# 06_POWER_5.net
KiCad netlist of a schematic drawn in Altium Designer
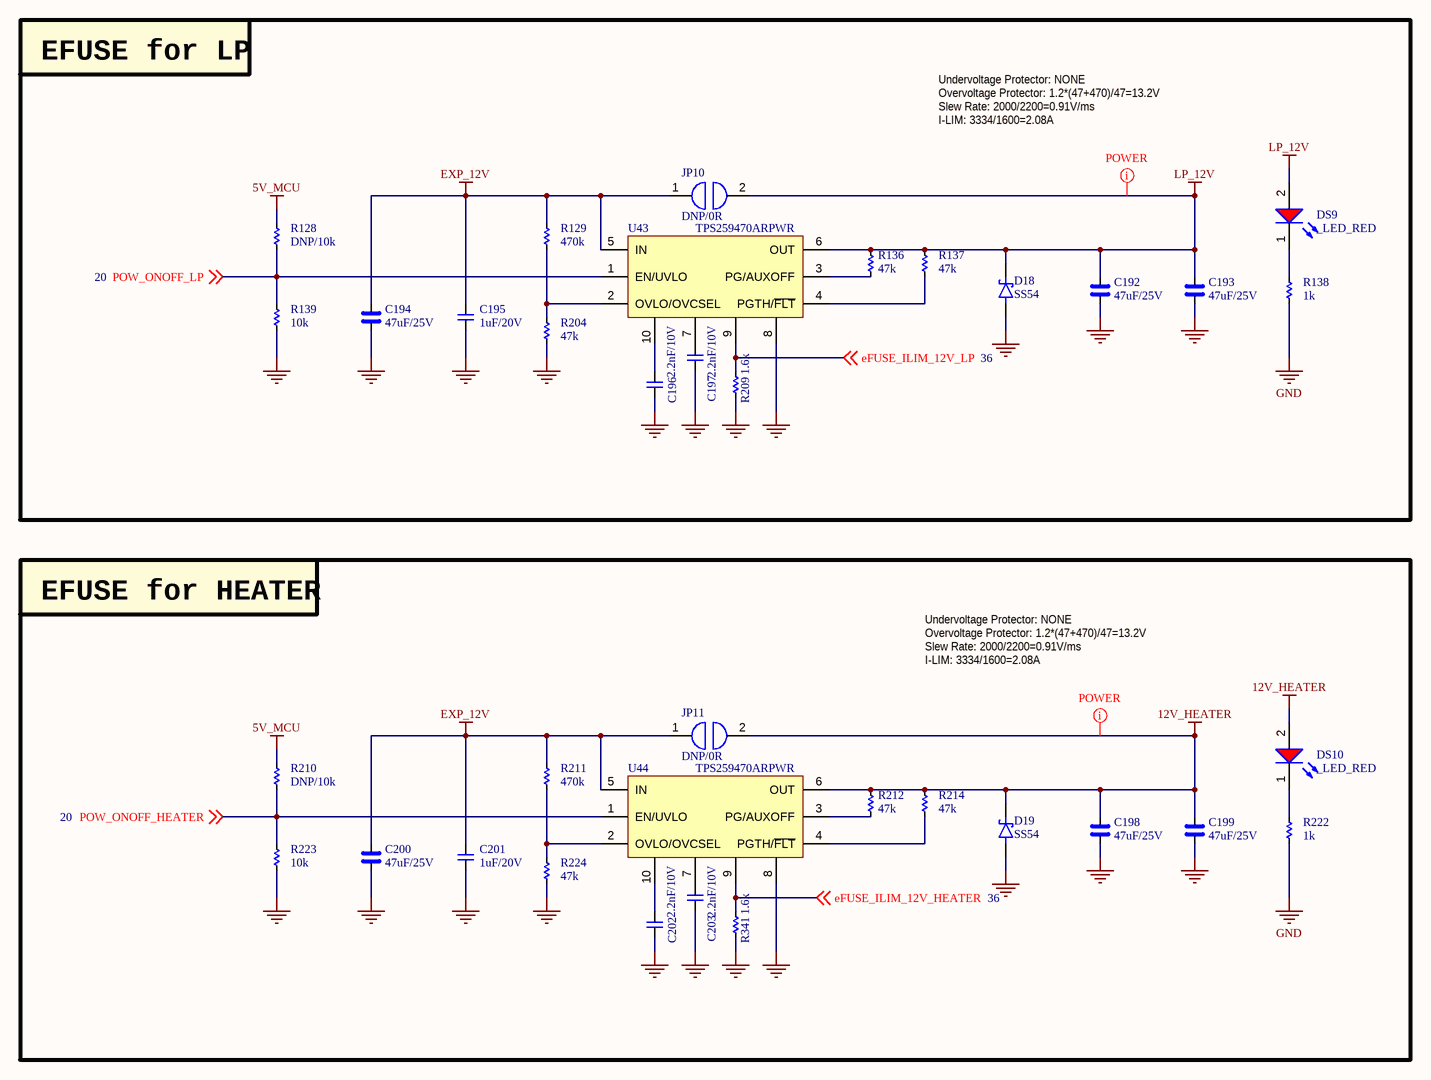
[diagram p0: 06_POWER_5.SchDoc]

(export (version "E")
  (design (tool "Eeschema 10.0.6"))
  (components
    (comp (ref "C192")
      (value "47uF/25V")
      (footprint "CAP_C_3225X80")
      (description "CAP High Value")
      (libsource (lib "LABLIB") (part "_CAP_C_High_2"))
    )
    (comp (ref "C193")
      (value "47uF/25V")
      (footprint "CAP_C_3225X80")
      (description "CAP High Value")
      (libsource (lib "LABLIB") (part "_CAP_C_High_2"))
    )
    (comp (ref "C194")
      (value "47uF/25V")
      (footprint "CAP_C_3225X80")
      (description "CAP High Value")
      (libsource (lib "LABLIB") (part "_CAP_C_High_2"))
    )
    (comp (ref "C195")
      (value "1uF/20V")
      (footprint "CAP_C_1005X60")
      (description "CAP")
      (libsource (lib "LABLIB") (part "_CAP_C_2"))
    )
    (comp (ref "C196")
      (value "2.2nF/10V")
      (footprint "CAP_C_1005X60")
      (description "CAP")
      (libsource (lib "LABLIB") (part "_CAP_C_2"))
    )
    (comp (ref "C197")
      (value "2.2nF/10V")
      (footprint "CAP_C_1005X60")
      (description "CAP")
      (libsource (lib "LABLIB") (part "_CAP_C_2"))
    )
    (comp (ref "C198")
      (value "47uF/25V")
      (footprint "CAP_C_3225X80")
      (description "CAP High Value")
      (libsource (lib "LABLIB") (part "_CAP_C_High_2"))
    )
    (comp (ref "C199")
      (value "47uF/25V")
      (footprint "CAP_C_3225X80")
      (description "CAP High Value")
      (libsource (lib "LABLIB") (part "_CAP_C_High_2"))
    )
    (comp (ref "C200")
      (value "47uF/25V")
      (footprint "CAP_C_3225X80")
      (description "CAP High Value")
      (libsource (lib "LABLIB") (part "_CAP_C_High_2"))
    )
    (comp (ref "C201")
      (value "1uF/20V")
      (footprint "CAP_C_1005X60")
      (description "CAP")
      (libsource (lib "LABLIB") (part "_CAP_C_2"))
    )
    (comp (ref "C202")
      (value "2.2nF/10V")
      (footprint "CAP_C_1005X60")
      (description "CAP")
      (libsource (lib "LABLIB") (part "_CAP_C_2"))
    )
    (comp (ref "C203")
      (value "2.2nF/10V")
      (footprint "CAP_C_1005X60")
      (description "CAP")
      (libsource (lib "LABLIB") (part "_CAP_C_2"))
    )
    (comp (ref "D18")
      (value "SS54")
      (footprint "DO-214AC_SMA")
      (description "DIODE SCHOTTKY")
      (libsource (lib "LABLIB") (part "DIODE SCHOTTKY"))
    )
    (comp (ref "D19")
      (value "SS54")
      (footprint "DO-214AC_SMA")
      (description "DIODE SCHOTTKY")
      (libsource (lib "LABLIB") (part "DIODE SCHOTTKY"))
    )
    (comp (ref "DS9") (value "_LED_RED") (footprint "LED_0603") (libsource (lib "LABLIB") (part "_LED_RED")))
    (comp (ref "DS10") (value "_LED_RED") (footprint "LED_0603") (libsource (lib "LABLIB") (part "_LED_RED")))
    (comp (ref "JP10") (value "DNP/0R") (footprint "JUMPER_1608") (libsource (lib "EXP_V1") (part "JUMPER")))
    (comp (ref "JP11") (value "DNP/0R") (footprint "JUMPER_1608") (libsource (lib "EXP_V1") (part "JUMPER")))
    (comp (ref "R128")
      (value "DNP/10k")
      (footprint "RES_C_1005X40")
      (description "RES")
      (libsource (lib "LABLIB") (part "_RES_B_2"))
    )
    (comp (ref "R129")
      (value "470k")
      (footprint "RES_C_1005X40")
      (description "RES")
      (libsource (lib "LABLIB") (part "_RES_B_2"))
    )
    (comp (ref "R136")
      (value "47k")
      (footprint "RES_C_1005X40")
      (description "RES")
      (libsource (lib "LABLIB") (part "_RES_B_2"))
    )
    (comp (ref "R137")
      (value "47k")
      (footprint "RES_C_1005X40")
      (description "RES")
      (libsource (lib "LABLIB") (part "_RES_B_2"))
    )
    (comp (ref "R138")
      (value "1k")
      (footprint "RES_C_1005X40")
      (description "RES")
      (libsource (lib "LABLIB") (part "_RES_B_2"))
    )
    (comp (ref "R139")
      (value "10k")
      (footprint "RES_C_1005X40")
      (description "RES")
      (libsource (lib "LABLIB") (part "_RES_B_2"))
    )
    (comp (ref "R204")
      (value "47k")
      (footprint "RES_C_1005X40")
      (description "RES")
      (libsource (lib "LABLIB") (part "_RES_B_2"))
    )
    (comp (ref "R209")
      (value "1.6k")
      (footprint "RES_C_1005X40")
      (description "RES")
      (libsource (lib "LABLIB") (part "_RES_B_2"))
    )
    (comp (ref "R210")
      (value "DNP/10k")
      (footprint "RES_C_1005X40")
      (description "RES")
      (libsource (lib "LABLIB") (part "_RES_B_2"))
    )
    (comp (ref "R211")
      (value "470k")
      (footprint "RES_C_1005X40")
      (description "RES")
      (libsource (lib "LABLIB") (part "_RES_B_2"))
    )
    (comp (ref "R212")
      (value "47k")
      (footprint "RES_C_1005X40")
      (description "RES")
      (libsource (lib "LABLIB") (part "_RES_B_2"))
    )
    (comp (ref "R214")
      (value "47k")
      (footprint "RES_C_1005X40")
      (description "RES")
      (libsource (lib "LABLIB") (part "_RES_B_2"))
    )
    (comp (ref "R222")
      (value "1k")
      (footprint "RES_C_1005X40")
      (description "RES")
      (libsource (lib "LABLIB") (part "_RES_B_2"))
    )
    (comp (ref "R223")
      (value "10k")
      (footprint "RES_C_1005X40")
      (description "RES")
      (libsource (lib "LABLIB") (part "_RES_B_2"))
    )
    (comp (ref "R224")
      (value "47k")
      (footprint "RES_C_1005X40")
      (description "RES")
      (libsource (lib "LABLIB") (part "_RES_B_2"))
    )
    (comp (ref "R341")
      (value "1.6k")
      (footprint "RES_C_1005X40")
      (description "RES")
      (libsource (lib "LABLIB") (part "_RES_B_2"))
    )
    (comp (ref "U43")
      (value "TPS259470ARPWR")
      (footprint "VQFN-HR-10")
      (libsource (lib "EXP_HW_V3") (part "TPS259470ARPWR"))
    )
    (comp (ref "U44")
      (value "TPS259470ARPWR")
      (footprint "VQFN-HR-10")
      (libsource (lib "EXP_HW_V3") (part "TPS259470ARPWR"))
    )
  )
  (nets
    (net (code "1") (name "5V_MCU") (class "Default")
      (node (ref "R128") (pin "1") (pinfunction "1_1") (pintype "passive"))
      (node (ref "R210") (pin "1") (pinfunction "1_1") (pintype "passive"))
    )
    (net (code "2") (name "12V_HEATER") (class "Default")
      (node (ref "C198") (pin "2") (pinfunction "2_2") (pintype "passive"))
      (node (ref "C199") (pin "2") (pinfunction "2_2") (pintype "passive"))
      (node (ref "D19") (pin "1") (pinfunction "K_1") (pintype "passive"))
      (node (ref "DS10") (pin "2") (pinfunction "A_2") (pintype "passive"))
      (node (ref "JP11") (pin "2") (pinfunction "2_2") (pintype "passive"))
      (node (ref "R212") (pin "2") (pinfunction "2_2") (pintype "passive"))
      (node (ref "R214") (pin "2") (pinfunction "2_2") (pintype "passive"))
      (node (ref "U44") (pin "6") (pinfunction "OUT_6") (pintype "passive"))
    )
    (net (code "3") (name "EXP_12V") (class "Default")
      (node (ref "C194") (pin "2") (pinfunction "2_2") (pintype "passive"))
      (node (ref "C195") (pin "2") (pinfunction "2_2") (pintype "passive"))
      (node (ref "C200") (pin "2") (pinfunction "2_2") (pintype "passive"))
      (node (ref "C201") (pin "2") (pinfunction "2_2") (pintype "passive"))
      (node (ref "JP10") (pin "1") (pinfunction "1_1") (pintype "passive"))
      (node (ref "JP11") (pin "1") (pinfunction "1_1") (pintype "passive"))
      (node (ref "R129") (pin "2") (pinfunction "2_2") (pintype "passive"))
      (node (ref "R211") (pin "2") (pinfunction "2_2") (pintype "passive"))
      (node (ref "U43") (pin "5") (pinfunction "IN_5") (pintype "passive"))
      (node (ref "U44") (pin "5") (pinfunction "IN_5") (pintype "passive"))
    )
    (net (code "4") (name "GND") (class "Default")
      (node (ref "C192") (pin "1") (pinfunction "1_1") (pintype "passive"))
      (node (ref "C193") (pin "1") (pinfunction "1_1") (pintype "passive"))
      (node (ref "C194") (pin "1") (pinfunction "1_1") (pintype "passive"))
      (node (ref "C195") (pin "1") (pinfunction "1_1") (pintype "passive"))
      (node (ref "C196") (pin "1") (pinfunction "1_1") (pintype "passive"))
      (node (ref "C197") (pin "1") (pinfunction "1_1") (pintype "passive"))
      (node (ref "C198") (pin "1") (pinfunction "1_1") (pintype "passive"))
      (node (ref "C199") (pin "1") (pinfunction "1_1") (pintype "passive"))
      (node (ref "C200") (pin "1") (pinfunction "1_1") (pintype "passive"))
      (node (ref "C201") (pin "1") (pinfunction "1_1") (pintype "passive"))
      (node (ref "C202") (pin "1") (pinfunction "1_1") (pintype "passive"))
      (node (ref "C203") (pin "1") (pinfunction "1_1") (pintype "passive"))
      (node (ref "D18") (pin "2") (pinfunction "A_2") (pintype "passive"))
      (node (ref "D19") (pin "2") (pinfunction "A_2") (pintype "passive"))
      (node (ref "R138") (pin "1") (pinfunction "1_1") (pintype "passive"))
      (node (ref "R139") (pin "2") (pinfunction "2_2") (pintype "passive"))
      (node (ref "R204") (pin "1") (pinfunction "1_1") (pintype "passive"))
      (node (ref "R209") (pin "1") (pinfunction "1_1") (pintype "passive"))
      (node (ref "R222") (pin "1") (pinfunction "1_1") (pintype "passive"))
      (node (ref "R223") (pin "2") (pinfunction "2_2") (pintype "passive"))
      (node (ref "R224") (pin "1") (pinfunction "1_1") (pintype "passive"))
      (node (ref "R341") (pin "1") (pinfunction "1_1") (pintype "passive"))
      (node (ref "U43") (pin "8") (pinfunction "8_8") (pintype "passive"))
      (node (ref "U44") (pin "8") (pinfunction "8_8") (pintype "passive"))
    )
    (net (code "5") (name "LP_12V") (class "Default")
      (node (ref "C192") (pin "2") (pinfunction "2_2") (pintype "passive"))
      (node (ref "C193") (pin "2") (pinfunction "2_2") (pintype "passive"))
      (node (ref "D18") (pin "1") (pinfunction "K_1") (pintype "passive"))
      (node (ref "DS9") (pin "2") (pinfunction "A_2") (pintype "passive"))
      (node (ref "JP10") (pin "2") (pinfunction "2_2") (pintype "passive"))
      (node (ref "R136") (pin "2") (pinfunction "2_2") (pintype "passive"))
      (node (ref "R137") (pin "2") (pinfunction "2_2") (pintype "passive"))
      (node (ref "U43") (pin "6") (pinfunction "OUT_6") (pintype "passive"))
    )
    (net (code "6") (name "Net-(C196-Pad2)") (class "Default")
      (node (ref "C196") (pin "2") (pinfunction "2_2") (pintype "passive"))
      (node (ref "U43") (pin "10") (pinfunction "10_10") (pintype "passive"))
    )
    (net (code "7") (name "Net-(C197-Pad2)") (class "Default")
      (node (ref "C197") (pin "2") (pinfunction "2_2") (pintype "passive"))
      (node (ref "U43") (pin "7") (pinfunction "7_7") (pintype "passive"))
    )
    (net (code "8") (name "Net-(C202-Pad2)") (class "Default")
      (node (ref "C202") (pin "2") (pinfunction "2_2") (pintype "passive"))
      (node (ref "U44") (pin "10") (pinfunction "10_10") (pintype "passive"))
    )
    (net (code "9") (name "Net-(C203-Pad2)") (class "Default")
      (node (ref "C203") (pin "2") (pinfunction "2_2") (pintype "passive"))
      (node (ref "U44") (pin "7") (pinfunction "7_7") (pintype "passive"))
    )
    (net (code "10") (name "Net-(DS9-K)") (class "Default")
      (node (ref "DS9") (pin "1") (pinfunction "K_1") (pintype "passive"))
      (node (ref "R138") (pin "2") (pinfunction "2_2") (pintype "passive"))
    )
    (net (code "11") (name "Net-(DS10-K)") (class "Default")
      (node (ref "DS10") (pin "1") (pinfunction "K_1") (pintype "passive"))
      (node (ref "R222") (pin "2") (pinfunction "2_2") (pintype "passive"))
    )
    (net (code "12") (name "Net-(U43-OVLO{slash}OVCSEL)") (class "Default")
      (node (ref "R129") (pin "1") (pinfunction "1_1") (pintype "passive"))
      (node (ref "R204") (pin "2") (pinfunction "2_2") (pintype "passive"))
      (node (ref "U43") (pin "2") (pinfunction "OVLO/OVCSEL_2") (pintype "passive"))
    )
    (net (code "13") (name "Net-(U43-PGTH{slash}~{FLT})") (class "Default")
      (node (ref "R137") (pin "1") (pinfunction "1_1") (pintype "passive"))
      (node (ref "U43") (pin "4") (pinfunction "PGTH/~{FLT}_4") (pintype "passive"))
    )
    (net (code "14") (name "Net-(U43-PG{slash}AUXOFF)") (class "Default")
      (node (ref "R136") (pin "1") (pinfunction "1_1") (pintype "passive"))
      (node (ref "U43") (pin "3") (pinfunction "PG/AUXOFF_3") (pintype "passive"))
    )
    (net (code "15") (name "Net-(U44-OVLO{slash}OVCSEL)") (class "Default")
      (node (ref "R211") (pin "1") (pinfunction "1_1") (pintype "passive"))
      (node (ref "R224") (pin "2") (pinfunction "2_2") (pintype "passive"))
      (node (ref "U44") (pin "2") (pinfunction "OVLO/OVCSEL_2") (pintype "passive"))
    )
    (net (code "16") (name "Net-(U44-PGTH{slash}~{FLT})") (class "Default")
      (node (ref "R214") (pin "1") (pinfunction "1_1") (pintype "passive"))
      (node (ref "U44") (pin "4") (pinfunction "PGTH/~{FLT}_4") (pintype "passive"))
    )
    (net (code "17") (name "Net-(U44-PG{slash}AUXOFF)") (class "Default")
      (node (ref "R212") (pin "1") (pinfunction "1_1") (pintype "passive"))
      (node (ref "U44") (pin "3") (pinfunction "PG/AUXOFF_3") (pintype "passive"))
    )
    (net (code "18") (name "POW_ONOFF_HEATER") (class "Default")
      (node (ref "R210") (pin "2") (pinfunction "2_2") (pintype "passive"))
      (node (ref "R223") (pin "1") (pinfunction "1_1") (pintype "passive"))
      (node (ref "U44") (pin "1") (pinfunction "EN/UVLO_1") (pintype "passive"))
    )
    (net (code "19") (name "POW_ONOFF_LP") (class "Default")
      (node (ref "R128") (pin "2") (pinfunction "2_2") (pintype "passive"))
      (node (ref "R139") (pin "1") (pinfunction "1_1") (pintype "passive"))
      (node (ref "U43") (pin "1") (pinfunction "EN/UVLO_1") (pintype "passive"))
    )
    (net (code "20") (name "eFUSE_ILIM_12V_HEATER") (class "Default")
      (node (ref "R341") (pin "2") (pinfunction "2_2") (pintype "passive"))
      (node (ref "U44") (pin "9") (pinfunction "9_9") (pintype "passive"))
    )
    (net (code "21") (name "eFUSE_ILIM_12V_LP") (class "Default")
      (node (ref "R209") (pin "2") (pinfunction "2_2") (pintype "passive"))
      (node (ref "U43") (pin "9") (pinfunction "9_9") (pintype "passive"))
    )
  )
)
